# EPS_FV1.net
KiCad netlist of a schematic drawn in EAGLE
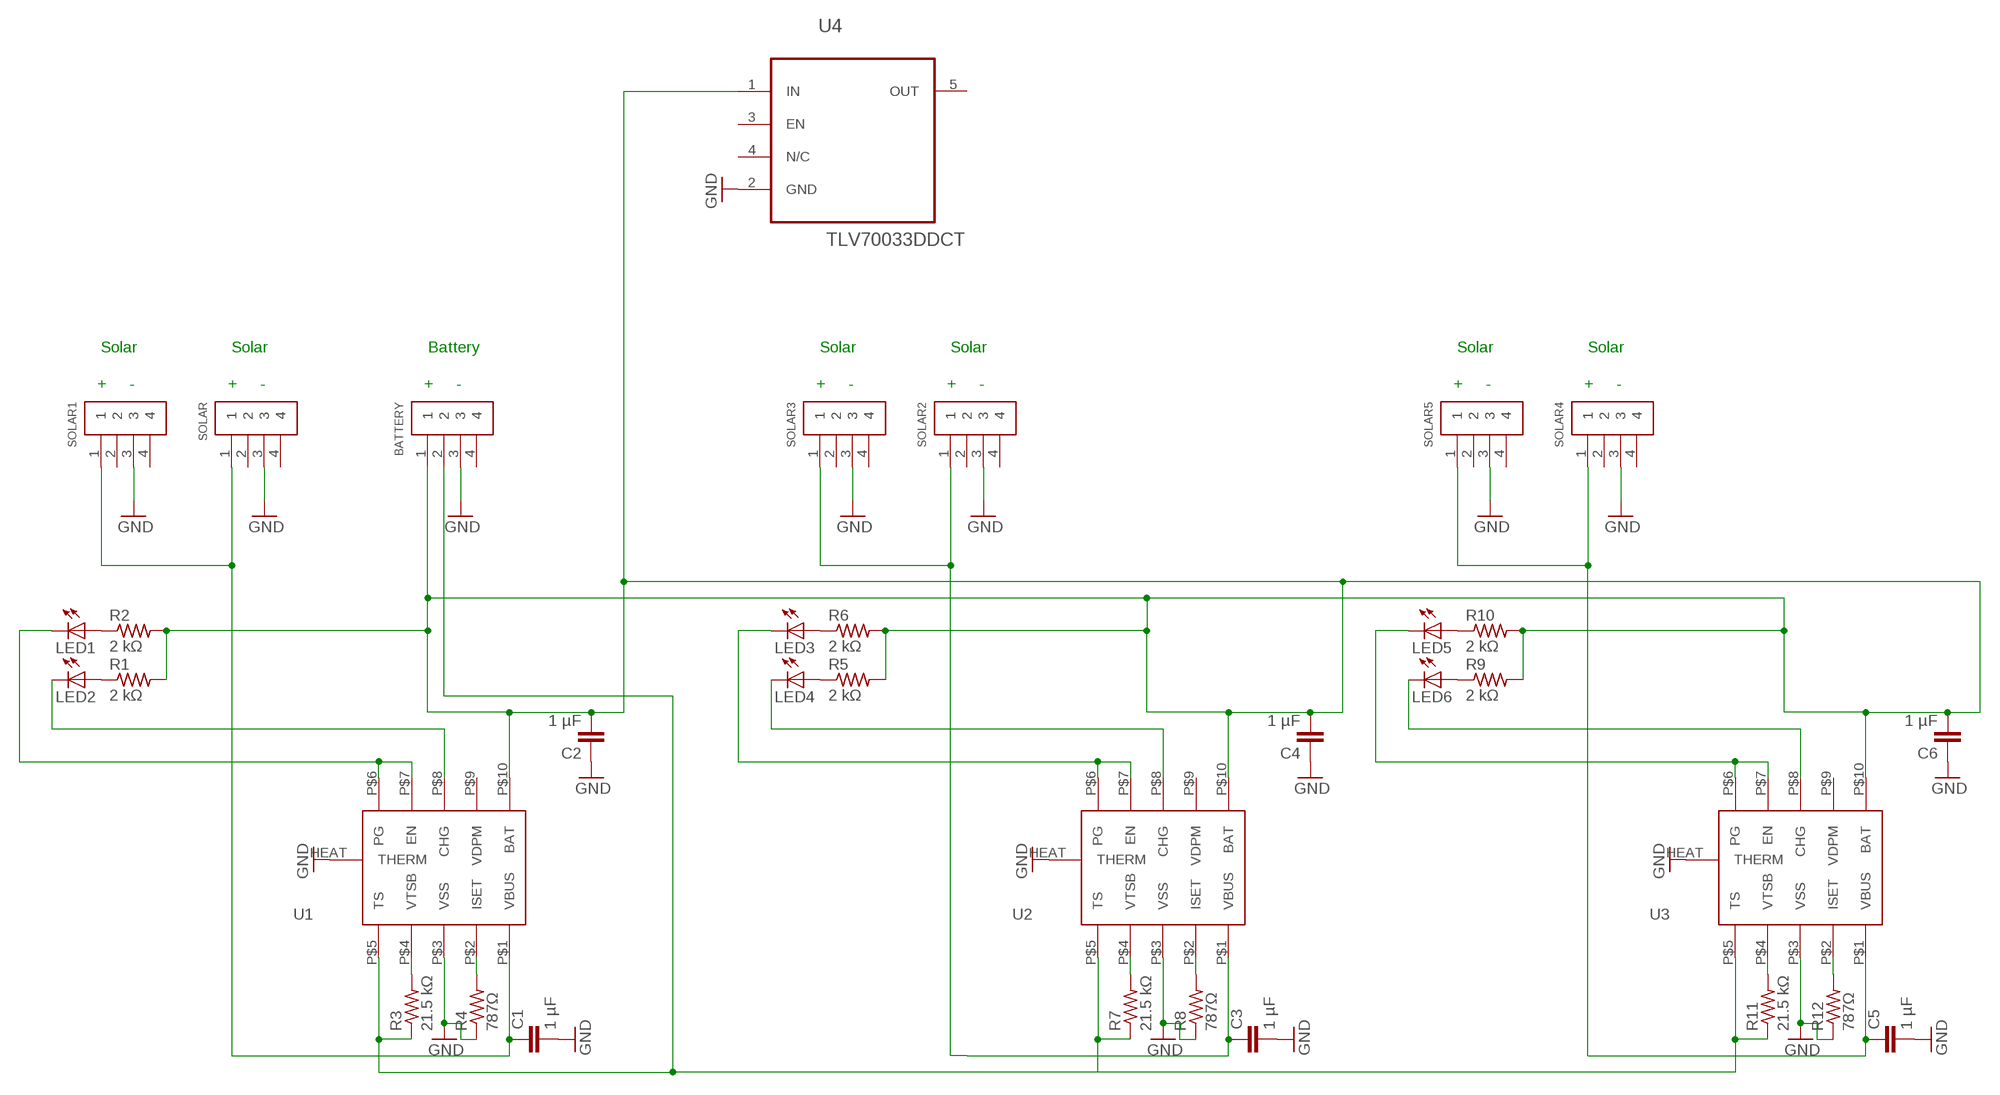
[diagram p0: schematic, sheet 1]

(export (version "E")
  (design (tool "Eeschema 10.0.6"))
  (components
    (comp (ref "BATTERY")
      (value "1X4-CLEANBIG")
      (footprint "eagle-import:1X04-CLEANBIG")
      (libsource (lib "eagle-import") (part "1X4-CLEANBIG"))
    )
    (comp (ref "C1")
      (value "1 µF")
      (footprint "eagle-import:C0805")
      (libsource (lib "eagle-import") (part "C-EUC0805"))
    )
    (comp (ref "C2")
      (value "1 µF")
      (footprint "eagle-import:C0805")
      (libsource (lib "eagle-import") (part "C-EUC0805"))
    )
    (comp (ref "C3")
      (value "1 µF")
      (footprint "eagle-import:C0805")
      (libsource (lib "eagle-import") (part "C-EUC0805"))
    )
    (comp (ref "C4")
      (value "1 µF")
      (footprint "eagle-import:C0805")
      (libsource (lib "eagle-import") (part "C-EUC0805"))
    )
    (comp (ref "C5")
      (value "1 µF")
      (footprint "eagle-import:C0805")
      (libsource (lib "eagle-import") (part "C-EUC0805"))
    )
    (comp (ref "C6")
      (value "1 µF")
      (footprint "eagle-import:C0805")
      (libsource (lib "eagle-import") (part "C-EUC0805"))
    )
    (comp (ref "LED1")
      (value "LEDCHIP-LED0805")
      (footprint "eagle-import:CHIP-LED0805")
      (libsource (lib "eagle-import") (part "LEDCHIP-LED0805"))
    )
    (comp (ref "LED2")
      (value "LEDCHIP-LED0805")
      (footprint "eagle-import:CHIP-LED0805")
      (libsource (lib "eagle-import") (part "LEDCHIP-LED0805"))
    )
    (comp (ref "LED3")
      (value "LEDCHIP-LED0805")
      (footprint "eagle-import:CHIP-LED0805")
      (libsource (lib "eagle-import") (part "LEDCHIP-LED0805"))
    )
    (comp (ref "LED4")
      (value "LEDCHIP-LED0805")
      (footprint "eagle-import:CHIP-LED0805")
      (libsource (lib "eagle-import") (part "LEDCHIP-LED0805"))
    )
    (comp (ref "LED5")
      (value "LEDCHIP-LED0805")
      (footprint "eagle-import:CHIP-LED0805")
      (libsource (lib "eagle-import") (part "LEDCHIP-LED0805"))
    )
    (comp (ref "LED6")
      (value "LEDCHIP-LED0805")
      (footprint "eagle-import:CHIP-LED0805")
      (libsource (lib "eagle-import") (part "LEDCHIP-LED0805"))
    )
    (comp (ref "R1")
      (value "2 kΩ")
      (footprint "eagle-import:R0805")
      (libsource (lib "eagle-import") (part "R-US_R0805"))
    )
    (comp (ref "R2")
      (value "2 kΩ")
      (footprint "eagle-import:R0805")
      (libsource (lib "eagle-import") (part "R-US_R0805"))
    )
    (comp (ref "R3")
      (value "21.5 kΩ")
      (footprint "eagle-import:R0805")
      (libsource (lib "eagle-import") (part "R-US_R0805"))
    )
    (comp (ref "R4")
      (value "787Ω")
      (footprint "eagle-import:R0805")
      (libsource (lib "eagle-import") (part "R-US_R0805"))
    )
    (comp (ref "R5")
      (value "2 kΩ")
      (footprint "eagle-import:R0805")
      (libsource (lib "eagle-import") (part "R-US_R0805"))
    )
    (comp (ref "R6")
      (value "2 kΩ")
      (footprint "eagle-import:R0805")
      (libsource (lib "eagle-import") (part "R-US_R0805"))
    )
    (comp (ref "R7")
      (value "21.5 kΩ")
      (footprint "eagle-import:R0805")
      (libsource (lib "eagle-import") (part "R-US_R0805"))
    )
    (comp (ref "R8")
      (value "787Ω")
      (footprint "eagle-import:R0805")
      (libsource (lib "eagle-import") (part "R-US_R0805"))
    )
    (comp (ref "R9")
      (value "2 kΩ")
      (footprint "eagle-import:R0805")
      (libsource (lib "eagle-import") (part "R-US_R0805"))
    )
    (comp (ref "R10")
      (value "2 kΩ")
      (footprint "eagle-import:R0805")
      (libsource (lib "eagle-import") (part "R-US_R0805"))
    )
    (comp (ref "R11")
      (value "21.5 kΩ")
      (footprint "eagle-import:R0805")
      (libsource (lib "eagle-import") (part "R-US_R0805"))
    )
    (comp (ref "R12")
      (value "787Ω")
      (footprint "eagle-import:R0805")
      (libsource (lib "eagle-import") (part "R-US_R0805"))
    )
    (comp (ref "SOLAR")
      (value "1X4-CLEANBIG")
      (footprint "eagle-import:1X04-CLEANBIG")
      (libsource (lib "eagle-import") (part "1X4-CLEANBIG"))
    )
    (comp (ref "SOLAR1")
      (value "1X4-CLEANBIG")
      (footprint "eagle-import:1X04-CLEANBIG")
      (libsource (lib "eagle-import") (part "1X4-CLEANBIG"))
    )
    (comp (ref "SOLAR2")
      (value "1X4-CLEANBIG")
      (footprint "eagle-import:1X04-CLEANBIG")
      (libsource (lib "eagle-import") (part "1X4-CLEANBIG"))
    )
    (comp (ref "SOLAR3")
      (value "1X4-CLEANBIG")
      (footprint "eagle-import:1X04-CLEANBIG")
      (libsource (lib "eagle-import") (part "1X4-CLEANBIG"))
    )
    (comp (ref "SOLAR4")
      (value "1X4-CLEANBIG")
      (footprint "eagle-import:1X04-CLEANBIG")
      (libsource (lib "eagle-import") (part "1X4-CLEANBIG"))
    )
    (comp (ref "SOLAR5")
      (value "1X4-CLEANBIG")
      (footprint "eagle-import:1X04-CLEANBIG")
      (libsource (lib "eagle-import") (part "1X4-CLEANBIG"))
    )
    (comp (ref "U1")
      (value "BQ24210")
      (footprint "eagle-import:BQ24210")
      (libsource (lib "eagle-import") (part "BQ24210"))
    )
    (comp (ref "U2")
      (value "BQ24210")
      (footprint "eagle-import:BQ24210")
      (libsource (lib "eagle-import") (part "BQ24210"))
    )
    (comp (ref "U3")
      (value "BQ24210")
      (footprint "eagle-import:BQ24210")
      (libsource (lib "eagle-import") (part "BQ24210"))
    )
    (comp (ref "U4")
      (value "TLV70033DDCT")
      (footprint "eagle-import:SOT95P280X110-5N")
      (libsource (lib "eagle-import") (part "TLV70033DDCT"))
    )
  )
  (nets
    (net (code "1") (name "GND") (class "Default")
      (node (ref "BATTERY") (pin "3") (pinfunction "3_3") (pintype "bidirectional"))
      (node (ref "C1") (pin "2") (pinfunction "2_2") (pintype "passive"))
      (node (ref "C2") (pin "1") (pinfunction "1_1") (pintype "passive"))
      (node (ref "C3") (pin "2") (pinfunction "2_2") (pintype "passive"))
      (node (ref "C4") (pin "1") (pinfunction "1_1") (pintype "passive"))
      (node (ref "C5") (pin "2") (pinfunction "2_2") (pintype "passive"))
      (node (ref "C6") (pin "1") (pinfunction "1_1") (pintype "passive"))
      (node (ref "R12") (pin "1") (pinfunction "1_1") (pintype "passive"))
      (node (ref "R4") (pin "1") (pinfunction "1_1") (pintype "passive"))
      (node (ref "R8") (pin "1") (pinfunction "1_1") (pintype "passive"))
      (node (ref "SOLAR") (pin "3") (pinfunction "3_3") (pintype "bidirectional"))
      (node (ref "SOLAR1") (pin "3") (pinfunction "3_3") (pintype "bidirectional"))
      (node (ref "SOLAR2") (pin "3") (pinfunction "3_3") (pintype "bidirectional"))
      (node (ref "SOLAR3") (pin "3") (pinfunction "3_3") (pintype "bidirectional"))
      (node (ref "SOLAR4") (pin "3") (pinfunction "3_3") (pintype "bidirectional"))
      (node (ref "SOLAR5") (pin "3") (pinfunction "3_3") (pintype "bidirectional"))
      (node (ref "U1") (pin "HEAT") (pinfunction "THERM_HEAT") (pintype "power_in"))
      (node (ref "U1") (pin "P$3") (pinfunction "VSS_P$3") (pintype "power_in"))
      (node (ref "U2") (pin "HEAT") (pinfunction "THERM_HEAT") (pintype "power_in"))
      (node (ref "U2") (pin "P$3") (pinfunction "VSS_P$3") (pintype "power_in"))
      (node (ref "U3") (pin "HEAT") (pinfunction "THERM_HEAT") (pintype "power_in"))
      (node (ref "U3") (pin "P$3") (pinfunction "VSS_P$3") (pintype "power_in"))
      (node (ref "U4") (pin "2") (pinfunction "GND_2") (pintype "passive"))
    )
    (net (code "2") (name "Net-(LED1-PadA)") (class "Default")
      (node (ref "LED1") (pin "A") (pinfunction "A_A") (pintype "passive"))
      (node (ref "R2") (pin "1") (pinfunction "1_1") (pintype "passive"))
    )
    (net (code "3") (name "Net-(LED2-PadA)") (class "Default")
      (node (ref "LED2") (pin "A") (pinfunction "A_A") (pintype "passive"))
      (node (ref "R1") (pin "1") (pinfunction "1_1") (pintype "passive"))
    )
    (net (code "4") (name "Net-(LED3-PadA)") (class "Default")
      (node (ref "LED3") (pin "A") (pinfunction "A_A") (pintype "passive"))
      (node (ref "R6") (pin "1") (pinfunction "1_1") (pintype "passive"))
    )
    (net (code "5") (name "Net-(LED4-PadA)") (class "Default")
      (node (ref "LED4") (pin "A") (pinfunction "A_A") (pintype "passive"))
      (node (ref "R5") (pin "1") (pinfunction "1_1") (pintype "passive"))
    )
    (net (code "6") (name "Net-(LED5-PadA)") (class "Default")
      (node (ref "LED5") (pin "A") (pinfunction "A_A") (pintype "passive"))
      (node (ref "R10") (pin "1") (pinfunction "1_1") (pintype "passive"))
    )
    (net (code "7") (name "Net-(LED6-PadA)") (class "Default")
      (node (ref "LED6") (pin "A") (pinfunction "A_A") (pintype "passive"))
      (node (ref "R9") (pin "1") (pinfunction "1_1") (pintype "passive"))
    )
    (net (code "8") (name "Net-(U1-BAT)") (class "Default")
      (node (ref "BATTERY") (pin "1") (pinfunction "1_1") (pintype "bidirectional"))
      (node (ref "C2") (pin "2") (pinfunction "2_2") (pintype "passive"))
      (node (ref "C4") (pin "2") (pinfunction "2_2") (pintype "passive"))
      (node (ref "C6") (pin "2") (pinfunction "2_2") (pintype "passive"))
      (node (ref "R1") (pin "2") (pinfunction "2_2") (pintype "passive"))
      (node (ref "R10") (pin "2") (pinfunction "2_2") (pintype "passive"))
      (node (ref "R2") (pin "2") (pinfunction "2_2") (pintype "passive"))
      (node (ref "R5") (pin "2") (pinfunction "2_2") (pintype "passive"))
      (node (ref "R6") (pin "2") (pinfunction "2_2") (pintype "passive"))
      (node (ref "R9") (pin "2") (pinfunction "2_2") (pintype "passive"))
      (node (ref "U1") (pin "P$10") (pinfunction "BAT_P$10") (pintype "bidirectional"))
      (node (ref "U2") (pin "P$10") (pinfunction "BAT_P$10") (pintype "bidirectional"))
      (node (ref "U3") (pin "P$10") (pinfunction "BAT_P$10") (pintype "bidirectional"))
      (node (ref "U4") (pin "1") (pinfunction "IN_1") (pintype "input"))
    )
    (net (code "9") (name "Net-(U1-CHG)") (class "Default")
      (node (ref "LED2") (pin "C") (pinfunction "C_C") (pintype "passive"))
      (node (ref "U1") (pin "P$8") (pinfunction "CHG_P$8") (pintype "output"))
    )
    (net (code "10") (name "Net-(U1-EN)") (class "Default")
      (node (ref "LED1") (pin "C") (pinfunction "C_C") (pintype "passive"))
      (node (ref "U1") (pin "P$6") (pinfunction "PG_P$6") (pintype "output"))
      (node (ref "U1") (pin "P$7") (pinfunction "EN_P$7") (pintype "input"))
    )
    (net (code "11") (name "Net-(U1-ISET)") (class "Default")
      (node (ref "R4") (pin "2") (pinfunction "2_2") (pintype "passive"))
      (node (ref "U1") (pin "P$2") (pinfunction "ISET_P$2") (pintype "input"))
    )
    (net (code "12") (name "Net-(U1-TS)") (class "Default")
      (node (ref "BATTERY") (pin "2") (pinfunction "2_2") (pintype "bidirectional"))
      (node (ref "R11") (pin "1") (pinfunction "1_1") (pintype "passive"))
      (node (ref "R3") (pin "1") (pinfunction "1_1") (pintype "passive"))
      (node (ref "R7") (pin "1") (pinfunction "1_1") (pintype "passive"))
      (node (ref "U1") (pin "P$5") (pinfunction "TS_P$5") (pintype "input"))
      (node (ref "U2") (pin "P$5") (pinfunction "TS_P$5") (pintype "input"))
      (node (ref "U3") (pin "P$5") (pinfunction "TS_P$5") (pintype "input"))
    )
    (net (code "13") (name "Net-(U1-VBUS)") (class "Default")
      (node (ref "C1") (pin "1") (pinfunction "1_1") (pintype "passive"))
      (node (ref "SOLAR") (pin "1") (pinfunction "1_1") (pintype "bidirectional"))
      (node (ref "SOLAR1") (pin "1") (pinfunction "1_1") (pintype "bidirectional"))
      (node (ref "U1") (pin "P$1") (pinfunction "VBUS_P$1") (pintype "bidirectional"))
    )
    (net (code "14") (name "Net-(U1-VTSB)") (class "Default")
      (node (ref "R3") (pin "2") (pinfunction "2_2") (pintype "passive"))
      (node (ref "U1") (pin "P$4") (pinfunction "VTSB_P$4") (pintype "output"))
    )
    (net (code "15") (name "Net-(U2-CHG)") (class "Default")
      (node (ref "LED4") (pin "C") (pinfunction "C_C") (pintype "passive"))
      (node (ref "U2") (pin "P$8") (pinfunction "CHG_P$8") (pintype "output"))
    )
    (net (code "16") (name "Net-(U2-EN)") (class "Default")
      (node (ref "LED3") (pin "C") (pinfunction "C_C") (pintype "passive"))
      (node (ref "U2") (pin "P$6") (pinfunction "PG_P$6") (pintype "output"))
      (node (ref "U2") (pin "P$7") (pinfunction "EN_P$7") (pintype "input"))
    )
    (net (code "17") (name "Net-(U2-ISET)") (class "Default")
      (node (ref "R8") (pin "2") (pinfunction "2_2") (pintype "passive"))
      (node (ref "U2") (pin "P$2") (pinfunction "ISET_P$2") (pintype "input"))
    )
    (net (code "18") (name "Net-(U2-VBUS)") (class "Default")
      (node (ref "C3") (pin "1") (pinfunction "1_1") (pintype "passive"))
      (node (ref "SOLAR2") (pin "1") (pinfunction "1_1") (pintype "bidirectional"))
      (node (ref "SOLAR3") (pin "1") (pinfunction "1_1") (pintype "bidirectional"))
      (node (ref "U2") (pin "P$1") (pinfunction "VBUS_P$1") (pintype "bidirectional"))
    )
    (net (code "19") (name "Net-(U2-VTSB)") (class "Default")
      (node (ref "R7") (pin "2") (pinfunction "2_2") (pintype "passive"))
      (node (ref "U2") (pin "P$4") (pinfunction "VTSB_P$4") (pintype "output"))
    )
    (net (code "20") (name "Net-(U3-CHG)") (class "Default")
      (node (ref "LED6") (pin "C") (pinfunction "C_C") (pintype "passive"))
      (node (ref "U3") (pin "P$8") (pinfunction "CHG_P$8") (pintype "output"))
    )
    (net (code "21") (name "Net-(U3-EN)") (class "Default")
      (node (ref "LED5") (pin "C") (pinfunction "C_C") (pintype "passive"))
      (node (ref "U3") (pin "P$6") (pinfunction "PG_P$6") (pintype "output"))
      (node (ref "U3") (pin "P$7") (pinfunction "EN_P$7") (pintype "input"))
    )
    (net (code "22") (name "Net-(U3-ISET)") (class "Default")
      (node (ref "R12") (pin "2") (pinfunction "2_2") (pintype "passive"))
      (node (ref "U3") (pin "P$2") (pinfunction "ISET_P$2") (pintype "input"))
    )
    (net (code "23") (name "Net-(U3-VBUS)") (class "Default")
      (node (ref "C5") (pin "1") (pinfunction "1_1") (pintype "passive"))
      (node (ref "SOLAR4") (pin "1") (pinfunction "1_1") (pintype "bidirectional"))
      (node (ref "SOLAR5") (pin "1") (pinfunction "1_1") (pintype "bidirectional"))
      (node (ref "U3") (pin "P$1") (pinfunction "VBUS_P$1") (pintype "bidirectional"))
    )
    (net (code "24") (name "Net-(U3-VTSB)") (class "Default")
      (node (ref "R11") (pin "2") (pinfunction "2_2") (pintype "passive"))
      (node (ref "U3") (pin "P$4") (pinfunction "VTSB_P$4") (pintype "output"))
    )
    (net (code "25") (name "unconnected-(BATTERY-Pad4)") (class "Default")
      (node (ref "BATTERY") (pin "4") (pinfunction "4_4") (pintype "bidirectional"))
    )
    (net (code "26") (name "unconnected-(SOLAR-Pad2)") (class "Default")
      (node (ref "SOLAR") (pin "2") (pinfunction "2_2") (pintype "bidirectional"))
    )
    (net (code "27") (name "unconnected-(SOLAR-Pad4)") (class "Default")
      (node (ref "SOLAR") (pin "4") (pinfunction "4_4") (pintype "bidirectional"))
    )
    (net (code "28") (name "unconnected-(SOLAR1-Pad2)") (class "Default")
      (node (ref "SOLAR1") (pin "2") (pinfunction "2_2") (pintype "bidirectional"))
    )
    (net (code "29") (name "unconnected-(SOLAR1-Pad4)") (class "Default")
      (node (ref "SOLAR1") (pin "4") (pinfunction "4_4") (pintype "bidirectional"))
    )
    (net (code "30") (name "unconnected-(SOLAR2-Pad2)") (class "Default")
      (node (ref "SOLAR2") (pin "2") (pinfunction "2_2") (pintype "bidirectional"))
    )
    (net (code "31") (name "unconnected-(SOLAR2-Pad4)") (class "Default")
      (node (ref "SOLAR2") (pin "4") (pinfunction "4_4") (pintype "bidirectional"))
    )
    (net (code "32") (name "unconnected-(SOLAR3-Pad2)") (class "Default")
      (node (ref "SOLAR3") (pin "2") (pinfunction "2_2") (pintype "bidirectional"))
    )
    (net (code "33") (name "unconnected-(SOLAR3-Pad4)") (class "Default")
      (node (ref "SOLAR3") (pin "4") (pinfunction "4_4") (pintype "bidirectional"))
    )
    (net (code "34") (name "unconnected-(SOLAR4-Pad2)") (class "Default")
      (node (ref "SOLAR4") (pin "2") (pinfunction "2_2") (pintype "bidirectional"))
    )
    (net (code "35") (name "unconnected-(SOLAR4-Pad4)") (class "Default")
      (node (ref "SOLAR4") (pin "4") (pinfunction "4_4") (pintype "bidirectional"))
    )
    (net (code "36") (name "unconnected-(SOLAR5-Pad2)") (class "Default")
      (node (ref "SOLAR5") (pin "2") (pinfunction "2_2") (pintype "bidirectional"))
    )
    (net (code "37") (name "unconnected-(SOLAR5-Pad4)") (class "Default")
      (node (ref "SOLAR5") (pin "4") (pinfunction "4_4") (pintype "bidirectional"))
    )
    (net (code "38") (name "unconnected-(U1-VDPM-PadP$9)") (class "Default")
      (node (ref "U1") (pin "P$9") (pinfunction "VDPM_P$9") (pintype "input"))
    )
    (net (code "39") (name "unconnected-(U2-VDPM-PadP$9)") (class "Default")
      (node (ref "U2") (pin "P$9") (pinfunction "VDPM_P$9") (pintype "input"))
    )
    (net (code "40") (name "unconnected-(U3-VDPM-PadP$9)") (class "Default")
      (node (ref "U3") (pin "P$9") (pinfunction "VDPM_P$9") (pintype "input"))
    )
    (net (code "41") (name "unconnected-(U4-EN-Pad3)") (class "Default")
      (node (ref "U4") (pin "3") (pinfunction "EN_3") (pintype "input"))
    )
    (net (code "42") (name "unconnected-(U4-N{slash}C-Pad4)") (class "Default")
      (node (ref "U4") (pin "4") (pinfunction "N/C_4") (pintype "no_connect"))
    )
    (net (code "43") (name "unconnected-(U4-OUT-Pad5)") (class "Default")
      (node (ref "U4") (pin "5") (pinfunction "OUT_5") (pintype "output"))
    )
  )
)
